# MeterMaid.net
KiCad netlist of a schematic drawn in EAGLE
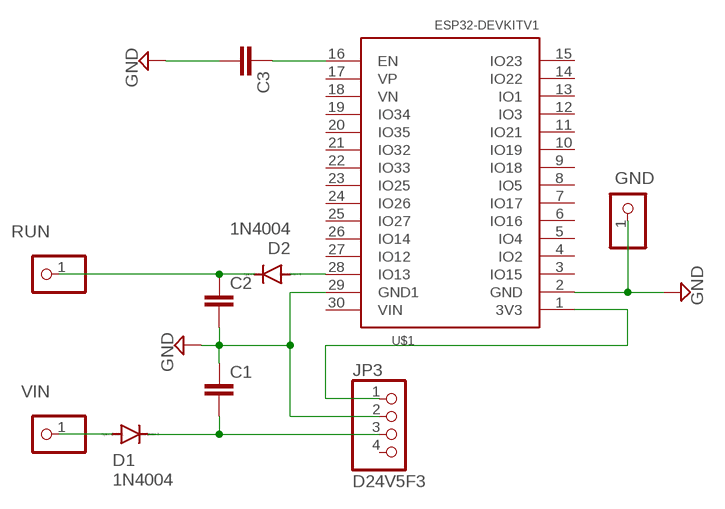
[diagram p0: schematic, sheet 1]

(export (version "E")
  (design (tool "Eeschema 10.0.6"))
  (components
    (comp (ref "C1")
      (value "C-EU025-050X050")
      (footprint "eagle-import:C025-050X050")
      (libsource (lib "eagle-import") (part "C-EU025-050X050"))
    )
    (comp (ref "C2")
      (value "C-EU025-050X050")
      (footprint "eagle-import:C025-050X050")
      (libsource (lib "eagle-import") (part "C-EU025-050X050"))
    )
    (comp (ref "C3")
      (value "C-EU025-050X050")
      (footprint "eagle-import:C025-050X050")
      (libsource (lib "eagle-import") (part "C-EU025-050X050"))
    )
    (comp (ref "D1")
      (value "1N4004")
      (footprint "eagle-import:DO41-10")
      (libsource (lib "eagle-import") (part "1N4004"))
    )
    (comp (ref "D2")
      (value "1N4004")
      (footprint "eagle-import:DO41-10")
      (libsource (lib "eagle-import") (part "1N4004"))
    )
    (comp (ref "GND")
      (value "PINHD-1X1")
      (footprint "eagle-import:1X01")
      (libsource (lib "eagle-import") (part "PINHD-1X1"))
    )
    (comp (ref "JP3")
      (value "D24V5F3")
      (footprint "eagle-import:1X04")
      (libsource (lib "eagle-import") (part "PINHD-1X4"))
    )
    (comp (ref "RUN")
      (value "PINHD-1X1")
      (footprint "eagle-import:1X01")
      (libsource (lib "eagle-import") (part "PINHD-1X1"))
    )
    (comp (ref "U$1")
      (value "ESP32DEVKITV1")
      (footprint "eagle-import:ESP32-DEVKITV1")
      (libsource (lib "eagle-import") (part "ESP32DEVKITV1"))
    )
    (comp (ref "VIN")
      (value "PINHD-1X1")
      (footprint "eagle-import:1X01")
      (libsource (lib "eagle-import") (part "PINHD-1X1"))
    )
  )
  (nets
    (net (code "1") (name "GND") (class "Default")
      (node (ref "C1") (pin "1") (pinfunction "1_1") (pintype "passive"))
      (node (ref "C2") (pin "2") (pinfunction "2_2") (pintype "passive"))
      (node (ref "C3") (pin "2") (pinfunction "2_2") (pintype "passive"))
      (node (ref "GND") (pin "1") (pinfunction "1_1") (pintype "passive"))
      (node (ref "JP3") (pin "2") (pinfunction "2_2") (pintype "passive"))
      (node (ref "U$1") (pin "2") (pinfunction "GND_2") (pintype "bidirectional"))
      (node (ref "U$1") (pin "29") (pinfunction "GND1_29") (pintype "bidirectional"))
    )
    (net (code "2") (name "Net-(C1-Pad2)") (class "Default")
      (node (ref "C1") (pin "2") (pinfunction "2_2") (pintype "passive"))
      (node (ref "D1") (pin "C") (pinfunction "C_C") (pintype "passive"))
      (node (ref "JP3") (pin "3") (pinfunction "3_3") (pintype "passive"))
    )
    (net (code "3") (name "Net-(C2-Pad1)") (class "Default")
      (node (ref "C2") (pin "1") (pinfunction "1_1") (pintype "passive"))
      (node (ref "D2") (pin "C") (pinfunction "C_C") (pintype "passive"))
      (node (ref "RUN") (pin "1") (pinfunction "1_1") (pintype "passive"))
    )
    (net (code "4") (name "Net-(D1-PadA)") (class "Default")
      (node (ref "D1") (pin "A") (pinfunction "A_A") (pintype "passive"))
      (node (ref "VIN") (pin "1") (pinfunction "1_1") (pintype "passive"))
    )
    (net (code "5") (name "Net-(U$1-3V3)") (class "Default")
      (node (ref "JP3") (pin "1") (pinfunction "1_1") (pintype "passive"))
      (node (ref "U$1") (pin "1") (pinfunction "3V3_1") (pintype "bidirectional"))
    )
    (net (code "6") (name "Net-(U$1-EN)") (class "Default")
      (node (ref "C3") (pin "1") (pinfunction "1_1") (pintype "passive"))
      (node (ref "U$1") (pin "16") (pinfunction "EN_16") (pintype "bidirectional"))
    )
    (net (code "7") (name "Net-(U$1-IO13)") (class "Default")
      (node (ref "D2") (pin "A") (pinfunction "A_A") (pintype "passive"))
      (node (ref "U$1") (pin "28") (pinfunction "IO13_28") (pintype "bidirectional"))
    )
    (net (code "8") (name "unconnected-(JP3-Pad4)") (class "Default")
      (node (ref "JP3") (pin "4") (pinfunction "4_4") (pintype "passive"))
    )
    (net (code "9") (name "unconnected-(U$1-IO1-Pad13)") (class "Default")
      (node (ref "U$1") (pin "13") (pinfunction "IO1_13") (pintype "bidirectional"))
    )
    (net (code "10") (name "unconnected-(U$1-IO2-Pad4)") (class "Default")
      (node (ref "U$1") (pin "4") (pinfunction "IO2_4") (pintype "bidirectional"))
    )
    (net (code "11") (name "unconnected-(U$1-IO3-Pad12)") (class "Default")
      (node (ref "U$1") (pin "12") (pinfunction "IO3_12") (pintype "bidirectional"))
    )
    (net (code "12") (name "unconnected-(U$1-IO4-Pad5)") (class "Default")
      (node (ref "U$1") (pin "5") (pinfunction "IO4_5") (pintype "bidirectional"))
    )
    (net (code "13") (name "unconnected-(U$1-IO5-Pad8)") (class "Default")
      (node (ref "U$1") (pin "8") (pinfunction "IO5_8") (pintype "bidirectional"))
    )
    (net (code "14") (name "unconnected-(U$1-IO12-Pad27)") (class "Default")
      (node (ref "U$1") (pin "27") (pinfunction "IO12_27") (pintype "bidirectional"))
    )
    (net (code "15") (name "unconnected-(U$1-IO14-Pad26)") (class "Default")
      (node (ref "U$1") (pin "26") (pinfunction "IO14_26") (pintype "bidirectional"))
    )
    (net (code "16") (name "unconnected-(U$1-IO15-Pad3)") (class "Default")
      (node (ref "U$1") (pin "3") (pinfunction "IO15_3") (pintype "bidirectional"))
    )
    (net (code "17") (name "unconnected-(U$1-IO16-Pad6)") (class "Default")
      (node (ref "U$1") (pin "6") (pinfunction "IO16_6") (pintype "bidirectional"))
    )
    (net (code "18") (name "unconnected-(U$1-IO17-Pad7)") (class "Default")
      (node (ref "U$1") (pin "7") (pinfunction "IO17_7") (pintype "bidirectional"))
    )
    (net (code "19") (name "unconnected-(U$1-IO18-Pad9)") (class "Default")
      (node (ref "U$1") (pin "9") (pinfunction "IO18_9") (pintype "bidirectional"))
    )
    (net (code "20") (name "unconnected-(U$1-IO19-Pad10)") (class "Default")
      (node (ref "U$1") (pin "10") (pinfunction "IO19_10") (pintype "bidirectional"))
    )
    (net (code "21") (name "unconnected-(U$1-IO21-Pad11)") (class "Default")
      (node (ref "U$1") (pin "11") (pinfunction "IO21_11") (pintype "bidirectional"))
    )
    (net (code "22") (name "unconnected-(U$1-IO22-Pad14)") (class "Default")
      (node (ref "U$1") (pin "14") (pinfunction "IO22_14") (pintype "bidirectional"))
    )
    (net (code "23") (name "unconnected-(U$1-IO23-Pad15)") (class "Default")
      (node (ref "U$1") (pin "15") (pinfunction "IO23_15") (pintype "bidirectional"))
    )
    (net (code "24") (name "unconnected-(U$1-IO25-Pad23)") (class "Default")
      (node (ref "U$1") (pin "23") (pinfunction "IO25_23") (pintype "bidirectional"))
    )
    (net (code "25") (name "unconnected-(U$1-IO26-Pad24)") (class "Default")
      (node (ref "U$1") (pin "24") (pinfunction "IO26_24") (pintype "bidirectional"))
    )
    (net (code "26") (name "unconnected-(U$1-IO27-Pad25)") (class "Default")
      (node (ref "U$1") (pin "25") (pinfunction "IO27_25") (pintype "bidirectional"))
    )
    (net (code "27") (name "unconnected-(U$1-IO32-Pad21)") (class "Default")
      (node (ref "U$1") (pin "21") (pinfunction "IO32_21") (pintype "bidirectional"))
    )
    (net (code "28") (name "unconnected-(U$1-IO33-Pad22)") (class "Default")
      (node (ref "U$1") (pin "22") (pinfunction "IO33_22") (pintype "bidirectional"))
    )
    (net (code "29") (name "unconnected-(U$1-IO34-Pad19)") (class "Default")
      (node (ref "U$1") (pin "19") (pinfunction "IO34_19") (pintype "bidirectional"))
    )
    (net (code "30") (name "unconnected-(U$1-IO35-Pad20)") (class "Default")
      (node (ref "U$1") (pin "20") (pinfunction "IO35_20") (pintype "bidirectional"))
    )
    (net (code "31") (name "unconnected-(U$1-VIN-Pad30)") (class "Default")
      (node (ref "U$1") (pin "30") (pinfunction "VIN_30") (pintype "bidirectional"))
    )
    (net (code "32") (name "unconnected-(U$1-VN-Pad18)") (class "Default")
      (node (ref "U$1") (pin "18") (pinfunction "VN_18") (pintype "bidirectional"))
    )
    (net (code "33") (name "unconnected-(U$1-VP-Pad17)") (class "Default")
      (node (ref "U$1") (pin "17") (pinfunction "VP_17") (pintype "bidirectional"))
    )
  )
)
